# SCH_POC-StartStopInterrupt_2022-12-13.net
KiCad netlist of a schematic drawn in EasyEDA
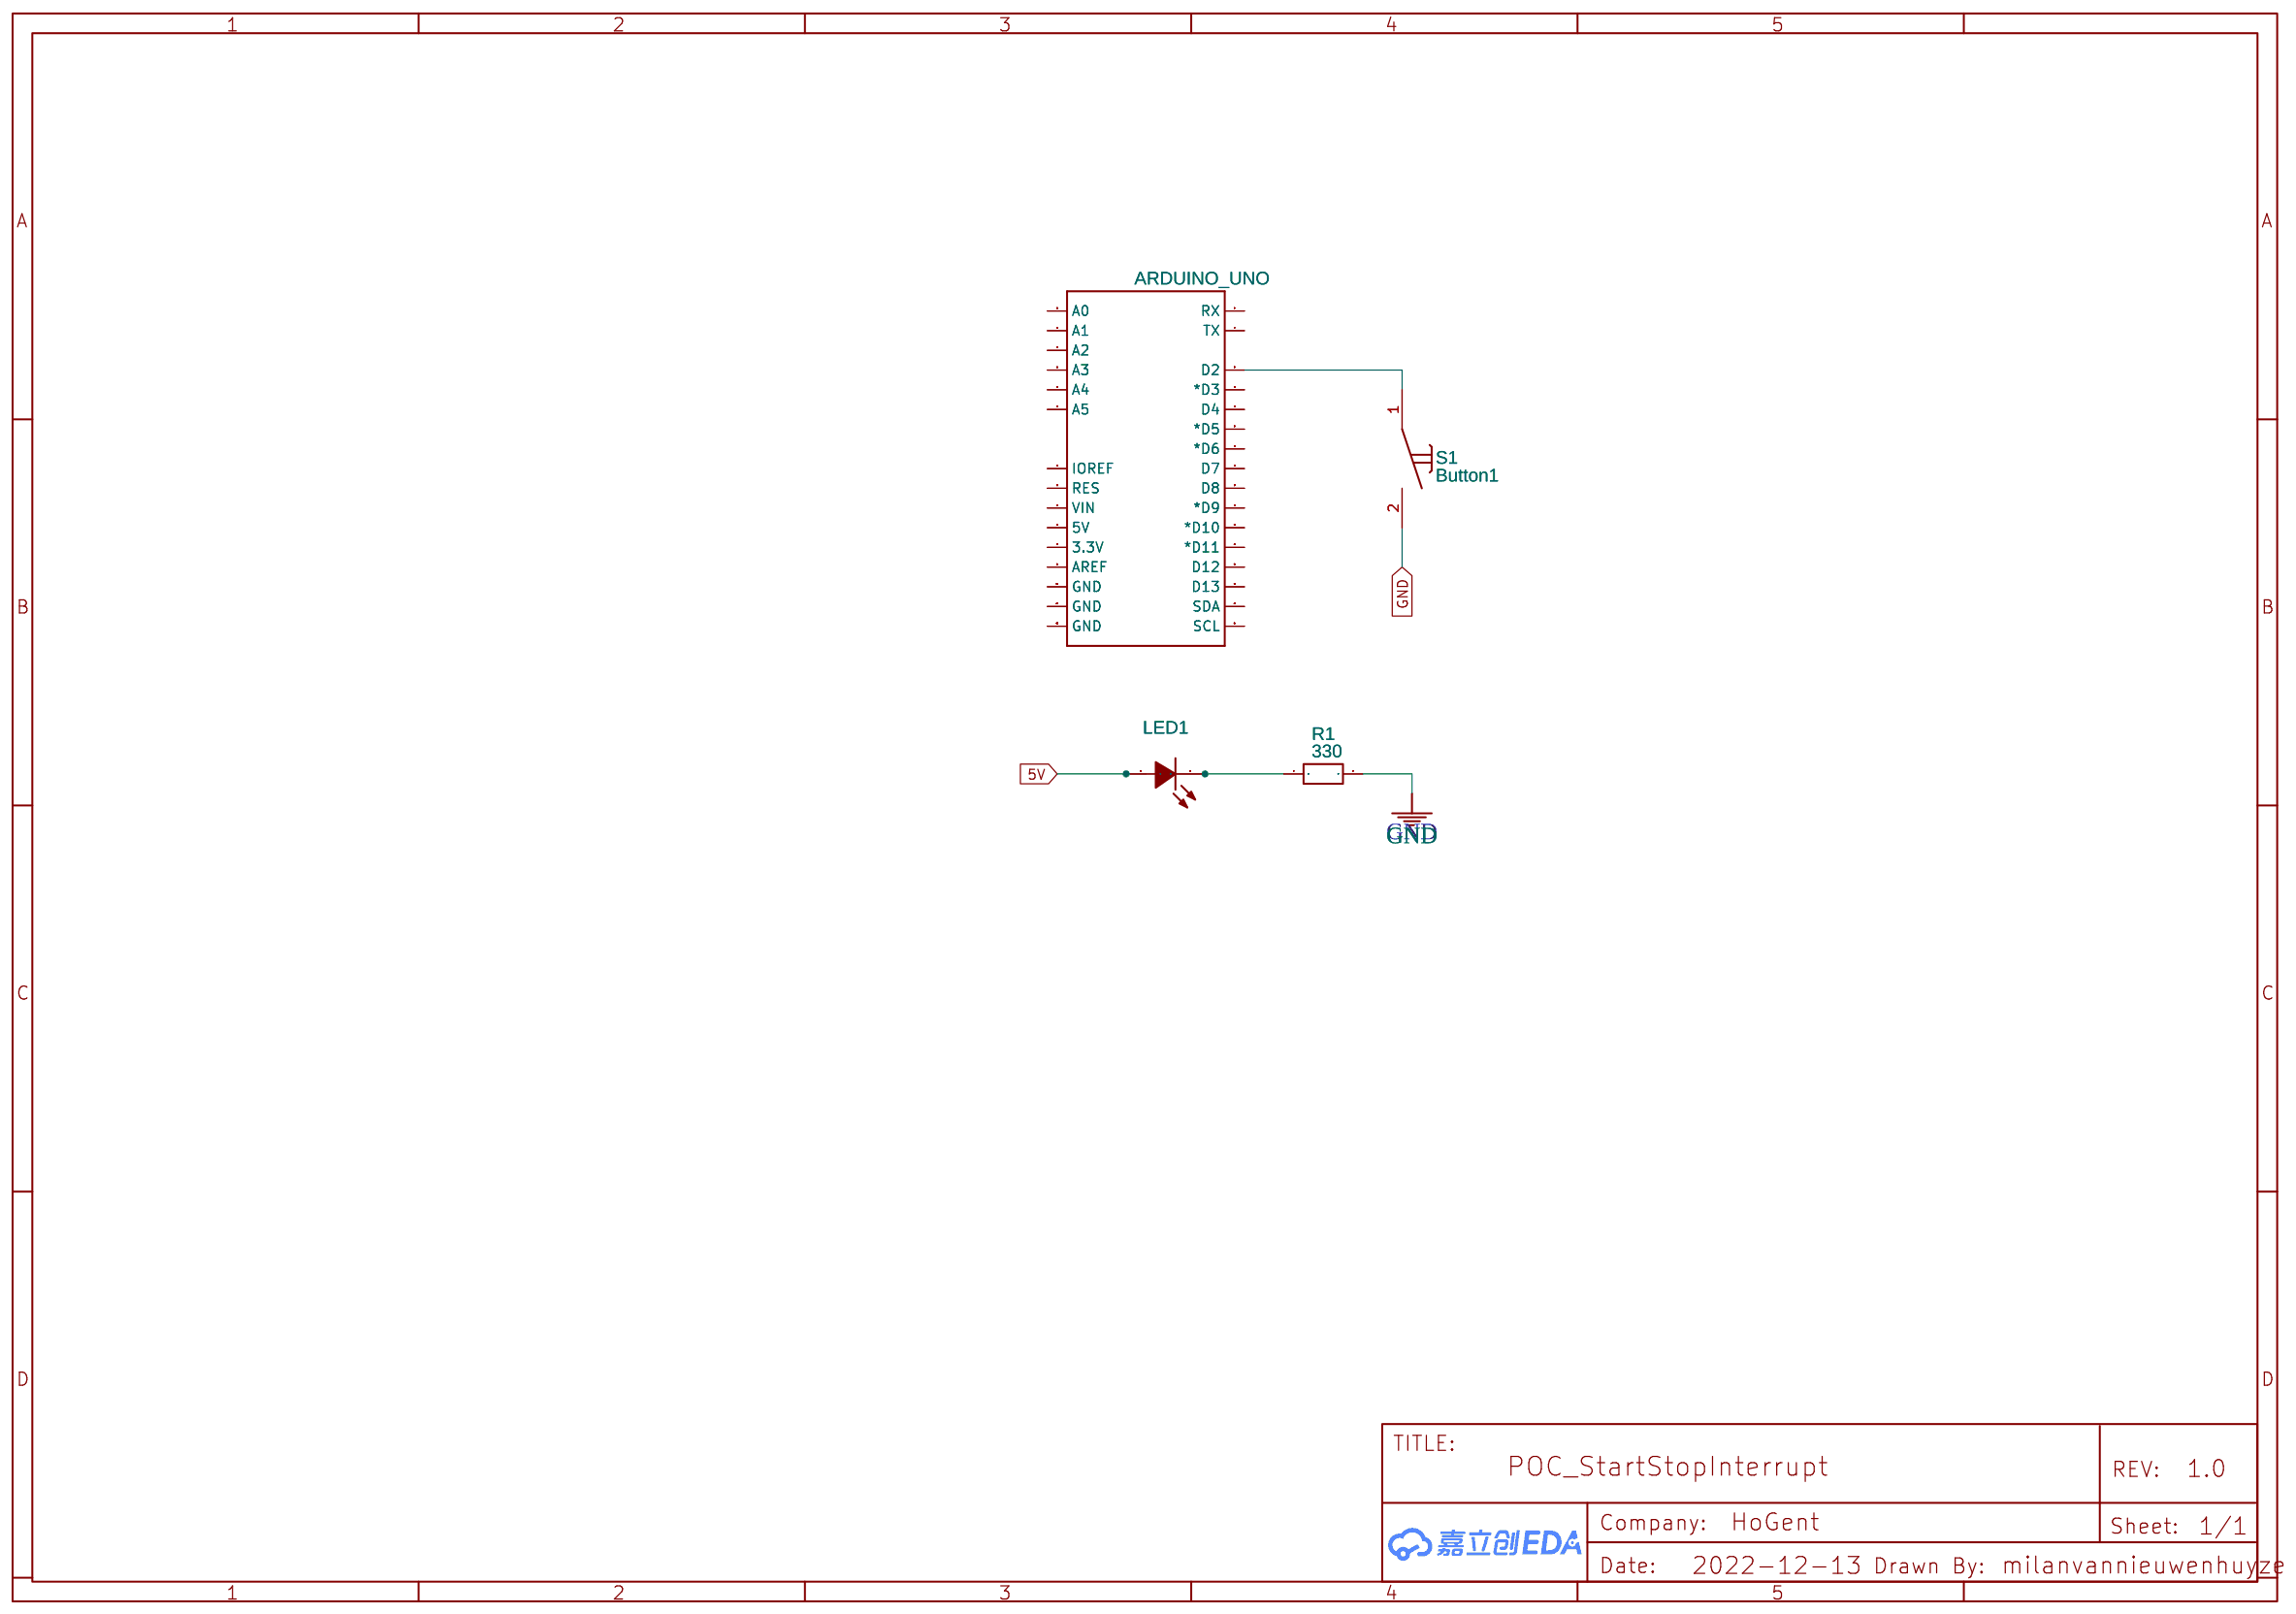
[diagram p0: schematic sheet]

(export (version "E")
  (design (tool "Eeschema 10.0.6"))
  (components
    (comp (ref "LED1")
      (value "BL-HUE35A-AV-TRE")
      (fields (field (name "BOM_Supplier Part") "C138549"))
      (libsource (lib "") (part "BL-HUE35A-AV-TRE"))
    )
    (comp (ref "R1") (value "330") (libsource (lib "") (part "R_0603_EU")))
    (comp (ref "S1") (value "Button1") (libsource (lib "") (part "Button1")))
    (comp (ref "U1") (value "ARDUINO_UNO") (libsource (lib "") (part "ARDUINO_R3_SHIELD")))
  )
  (nets
    (net (code "1") (name "5V") (class "Default")
      (node (ref "LED1") (pin "2") (pinfunction "A_2") (pintype "unspecified"))
    )
    (net (code "2") (name "GND") (class "Default")
      (node (ref "R1") (pin "2") (pinfunction "2_2") (pintype "unspecified"))
      (node (ref "S1") (pin "2") (pintype "unspecified"))
    )
    (net (code "3") (name "Net-(LED1-K)") (class "Default")
      (node (ref "LED1") (pin "1") (pinfunction "K_1") (pintype "unspecified"))
      (node (ref "R1") (pin "1") (pinfunction "1_1") (pintype "unspecified"))
    )
    (net (code "4") (name "Net-(S1-Pad1)") (class "Default")
      (node (ref "S1") (pin "1") (pintype "unspecified"))
      (node (ref "U1") (pin "D2") (pinfunction "D2_D2") (pintype "unspecified"))
    )
    (net (code "5") (name "unconnected-(U1-*D3-PadD3)") (class "Default")
      (node (ref "U1") (pin "D3") (pinfunction "*D3_D3") (pintype "unspecified"))
    )
    (net (code "6") (name "unconnected-(U1-*D5-PadD5)") (class "Default")
      (node (ref "U1") (pin "D5") (pinfunction "*D5_D5") (pintype "unspecified"))
    )
    (net (code "7") (name "unconnected-(U1-*D6-PadD6)") (class "Default")
      (node (ref "U1") (pin "D6") (pinfunction "*D6_D6") (pintype "unspecified"))
    )
    (net (code "8") (name "unconnected-(U1-*D9-PadD9)") (class "Default")
      (node (ref "U1") (pin "D9") (pinfunction "*D9_D9") (pintype "unspecified"))
    )
    (net (code "9") (name "unconnected-(U1-*D10-PadD10)") (class "Default")
      (node (ref "U1") (pin "D10") (pinfunction "*D10_D10") (pintype "unspecified"))
    )
    (net (code "10") (name "unconnected-(U1-*D11-PadD11)") (class "Default")
      (node (ref "U1") (pin "D11") (pinfunction "*D11_D11") (pintype "unspecified"))
    )
    (net (code "11") (name "unconnected-(U1-GND-PadGND@0)") (class "Default")
      (node (ref "U1") (pin "GND@0") (pinfunction "GND_GND@0") (pintype "unspecified"))
    )
    (net (code "12") (name "unconnected-(U1-GND-PadGND@1)") (class "Default")
      (node (ref "U1") (pin "GND@1") (pinfunction "GND_GND@1") (pintype "unspecified"))
    )
    (net (code "13") (name "unconnected-(U1-GND-PadGND@2)") (class "Default")
      (node (ref "U1") (pin "GND@2") (pinfunction "GND_GND@2") (pintype "unspecified"))
    )
    (net (code "14") (name "unconnected-(U1-Pad3.3V)") (class "Default")
      (node (ref "U1") (pin "3.3V") (pinfunction "3.3V_3.3V") (pintype "unspecified"))
    )
    (net (code "15") (name "unconnected-(U1-Pad5V)") (class "Default")
      (node (ref "U1") (pin "5V") (pinfunction "5V_5V") (pintype "unspecified"))
    )
    (net (code "16") (name "unconnected-(U1-PadA0)") (class "Default")
      (node (ref "U1") (pin "A0") (pinfunction "A0_A0") (pintype "unspecified"))
    )
    (net (code "17") (name "unconnected-(U1-PadA1)") (class "Default")
      (node (ref "U1") (pin "A1") (pinfunction "A1_A1") (pintype "unspecified"))
    )
    (net (code "18") (name "unconnected-(U1-PadA2)") (class "Default")
      (node (ref "U1") (pin "A2") (pinfunction "A2_A2") (pintype "unspecified"))
    )
    (net (code "19") (name "unconnected-(U1-PadA3)") (class "Default")
      (node (ref "U1") (pin "A3") (pinfunction "A3_A3") (pintype "unspecified"))
    )
    (net (code "20") (name "unconnected-(U1-PadA4)") (class "Default")
      (node (ref "U1") (pin "A4") (pinfunction "A4_A4") (pintype "unspecified"))
    )
    (net (code "21") (name "unconnected-(U1-PadA5)") (class "Default")
      (node (ref "U1") (pin "A5") (pinfunction "A5_A5") (pintype "unspecified"))
    )
    (net (code "22") (name "unconnected-(U1-PadAREF)") (class "Default")
      (node (ref "U1") (pin "AREF") (pinfunction "AREF_AREF") (pintype "unspecified"))
    )
    (net (code "23") (name "unconnected-(U1-PadD4)") (class "Default")
      (node (ref "U1") (pin "D4") (pinfunction "D4_D4") (pintype "unspecified"))
    )
    (net (code "24") (name "unconnected-(U1-PadD7)") (class "Default")
      (node (ref "U1") (pin "D7") (pinfunction "D7_D7") (pintype "unspecified"))
    )
    (net (code "25") (name "unconnected-(U1-PadD8)") (class "Default")
      (node (ref "U1") (pin "D8") (pinfunction "D8_D8") (pintype "unspecified"))
    )
    (net (code "26") (name "unconnected-(U1-PadD12)") (class "Default")
      (node (ref "U1") (pin "D12") (pinfunction "D12_D12") (pintype "unspecified"))
    )
    (net (code "27") (name "unconnected-(U1-PadD13)") (class "Default")
      (node (ref "U1") (pin "D13") (pinfunction "D13_D13") (pintype "unspecified"))
    )
    (net (code "28") (name "unconnected-(U1-PadIOREF)") (class "Default")
      (node (ref "U1") (pin "IOREF") (pinfunction "IOREF_IOREF") (pintype "unspecified"))
    )
    (net (code "29") (name "unconnected-(U1-PadRES)") (class "Default")
      (node (ref "U1") (pin "RES") (pinfunction "RES_RES") (pintype "unspecified"))
    )
    (net (code "30") (name "unconnected-(U1-PadRX)") (class "Default")
      (node (ref "U1") (pin "RX") (pinfunction "RX_RX") (pintype "unspecified"))
    )
    (net (code "31") (name "unconnected-(U1-PadSCL)") (class "Default")
      (node (ref "U1") (pin "SCL") (pinfunction "SCL_SCL") (pintype "unspecified"))
    )
    (net (code "32") (name "unconnected-(U1-PadSDA)") (class "Default")
      (node (ref "U1") (pin "SDA") (pinfunction "SDA_SDA") (pintype "unspecified"))
    )
    (net (code "33") (name "unconnected-(U1-PadTX)") (class "Default")
      (node (ref "U1") (pin "TX") (pinfunction "TX_TX") (pintype "unspecified"))
    )
    (net (code "34") (name "unconnected-(U1-PadVIN)") (class "Default")
      (node (ref "U1") (pin "VIN") (pinfunction "VIN_VIN") (pintype "unspecified"))
    )
  )
)
